# panels_connections.net
KiCad netlist of a schematic drawn in Altium Designer
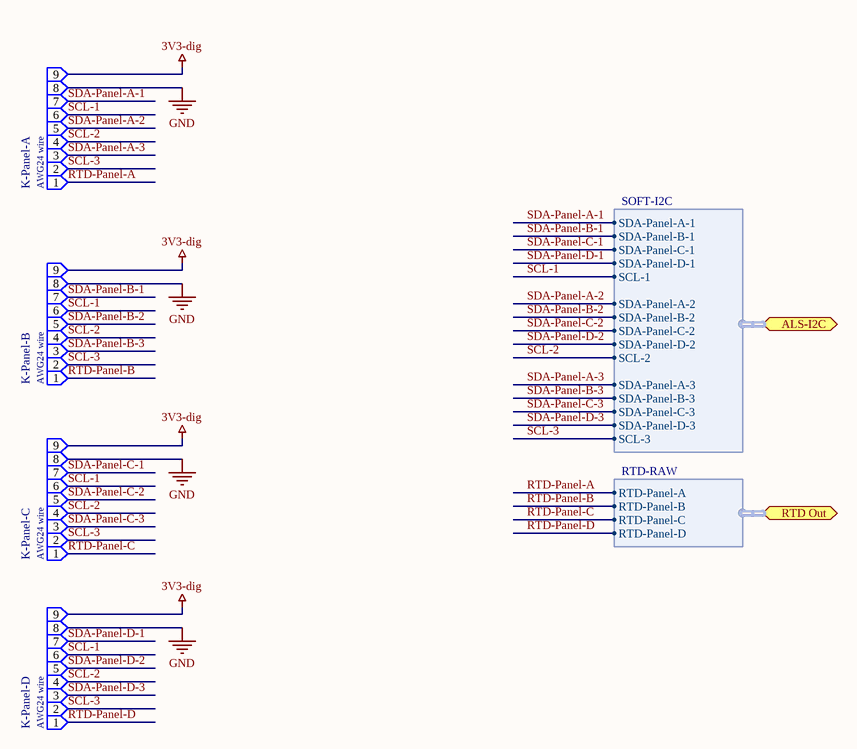
[diagram p0: panels_connections.SchDoc]

(export (version "E")
  (design (tool "Eeschema 10.0.6"))
  (components
    (comp (ref "K-Panel-A")
      (value "AWG24 wire")
      (footprint "wire-awg26-9_stress-relief")
      (description "Single wire AWG26 solder point.")
      (libsource (lib "connectors_printed-circuit-board") (part "wire-awg26-9"))
    )
    (comp (ref "K-Panel-B")
      (value "AWG24 wire")
      (footprint "wire-awg26-9_stress-relief")
      (description "Single wire AWG26 solder point.")
      (libsource (lib "connectors_printed-circuit-board") (part "wire-awg26-9"))
    )
    (comp (ref "K-Panel-C")
      (value "AWG24 wire")
      (footprint "wire-awg26-9_stress-relief")
      (description "Single wire AWG26 solder point.")
      (libsource (lib "connectors_printed-circuit-board") (part "wire-awg26-9"))
    )
    (comp (ref "K-Panel-D")
      (value "AWG24 wire")
      (footprint "wire-awg26-9_stress-relief")
      (description "Single wire AWG26 solder point.")
      (libsource (lib "connectors_printed-circuit-board") (part "wire-awg26-9"))
    )
  )
  (nets
    (net (code "3") (name "/RTD-Panel-A") (class "Default")
      (node (ref "K-Panel-A") (pin "1") (pinfunction "1_1") (pintype "passive"))
    )
    (net (code "4") (name "/RTD-Panel-B") (class "Default")
      (node (ref "K-Panel-B") (pin "1") (pinfunction "1_1") (pintype "passive"))
    )
    (net (code "5") (name "/RTD-Panel-C") (class "Default")
      (node (ref "K-Panel-C") (pin "1") (pinfunction "1_1") (pintype "passive"))
    )
    (net (code "6") (name "/RTD-Panel-D") (class "Default")
      (node (ref "K-Panel-D") (pin "1") (pinfunction "1_1") (pintype "passive"))
    )
    (net (code "7") (name "/SCL-1") (class "Default")
      (node (ref "K-Panel-A") (pin "6") (pinfunction "6_6") (pintype "passive"))
      (node (ref "K-Panel-B") (pin "6") (pinfunction "6_6") (pintype "passive"))
      (node (ref "K-Panel-C") (pin "6") (pinfunction "6_6") (pintype "passive"))
      (node (ref "K-Panel-D") (pin "6") (pinfunction "6_6") (pintype "passive"))
    )
    (net (code "8") (name "/SCL-2") (class "Default")
      (node (ref "K-Panel-A") (pin "4") (pinfunction "4_4") (pintype "passive"))
      (node (ref "K-Panel-B") (pin "4") (pinfunction "4_4") (pintype "passive"))
      (node (ref "K-Panel-C") (pin "4") (pinfunction "4_4") (pintype "passive"))
      (node (ref "K-Panel-D") (pin "4") (pinfunction "4_4") (pintype "passive"))
    )
    (net (code "9") (name "/SCL-3") (class "Default")
      (node (ref "K-Panel-A") (pin "2") (pinfunction "2_2") (pintype "passive"))
      (node (ref "K-Panel-B") (pin "2") (pinfunction "2_2") (pintype "passive"))
      (node (ref "K-Panel-C") (pin "2") (pinfunction "2_2") (pintype "passive"))
      (node (ref "K-Panel-D") (pin "2") (pinfunction "2_2") (pintype "passive"))
    )
    (net (code "10") (name "/SDA-Panel-A-1") (class "Default")
      (node (ref "K-Panel-A") (pin "7") (pinfunction "7_7") (pintype "passive"))
    )
    (net (code "11") (name "/SDA-Panel-A-2") (class "Default")
      (node (ref "K-Panel-A") (pin "5") (pinfunction "5_5") (pintype "passive"))
    )
    (net (code "12") (name "/SDA-Panel-A-3") (class "Default")
      (node (ref "K-Panel-A") (pin "3") (pinfunction "3_3") (pintype "passive"))
    )
    (net (code "13") (name "/SDA-Panel-B-1") (class "Default")
      (node (ref "K-Panel-B") (pin "7") (pinfunction "7_7") (pintype "passive"))
    )
    (net (code "14") (name "/SDA-Panel-B-2") (class "Default")
      (node (ref "K-Panel-B") (pin "5") (pinfunction "5_5") (pintype "passive"))
    )
    (net (code "15") (name "/SDA-Panel-B-3") (class "Default")
      (node (ref "K-Panel-B") (pin "3") (pinfunction "3_3") (pintype "passive"))
    )
    (net (code "16") (name "/SDA-Panel-C-1") (class "Default")
      (node (ref "K-Panel-C") (pin "7") (pinfunction "7_7") (pintype "passive"))
    )
    (net (code "17") (name "/SDA-Panel-C-2") (class "Default")
      (node (ref "K-Panel-C") (pin "5") (pinfunction "5_5") (pintype "passive"))
    )
    (net (code "18") (name "/SDA-Panel-C-3") (class "Default")
      (node (ref "K-Panel-C") (pin "3") (pinfunction "3_3") (pintype "passive"))
    )
    (net (code "19") (name "/SDA-Panel-D-1") (class "Default")
      (node (ref "K-Panel-D") (pin "7") (pinfunction "7_7") (pintype "passive"))
    )
    (net (code "20") (name "/SDA-Panel-D-2") (class "Default")
      (node (ref "K-Panel-D") (pin "5") (pinfunction "5_5") (pintype "passive"))
    )
    (net (code "21") (name "/SDA-Panel-D-3") (class "Default")
      (node (ref "K-Panel-D") (pin "3") (pinfunction "3_3") (pintype "passive"))
    )
    (net (code "24") (name "3V3-dig") (class "Default")
      (node (ref "K-Panel-A") (pin "9") (pinfunction "9_9") (pintype "passive"))
      (node (ref "K-Panel-B") (pin "9") (pinfunction "9_9") (pintype "passive"))
      (node (ref "K-Panel-C") (pin "9") (pinfunction "9_9") (pintype "passive"))
      (node (ref "K-Panel-D") (pin "9") (pinfunction "9_9") (pintype "passive"))
    )
    (net (code "25") (name "GND") (class "Default")
      (node (ref "K-Panel-A") (pin "8") (pinfunction "8_8") (pintype "passive"))
      (node (ref "K-Panel-B") (pin "8") (pinfunction "8_8") (pintype "passive"))
      (node (ref "K-Panel-C") (pin "8") (pinfunction "8_8") (pintype "passive"))
      (node (ref "K-Panel-D") (pin "8") (pinfunction "8_8") (pintype "passive"))
    )
  )
)
